# Tiny_Programmer.net
KiCad netlist of a schematic drawn in EAGLE
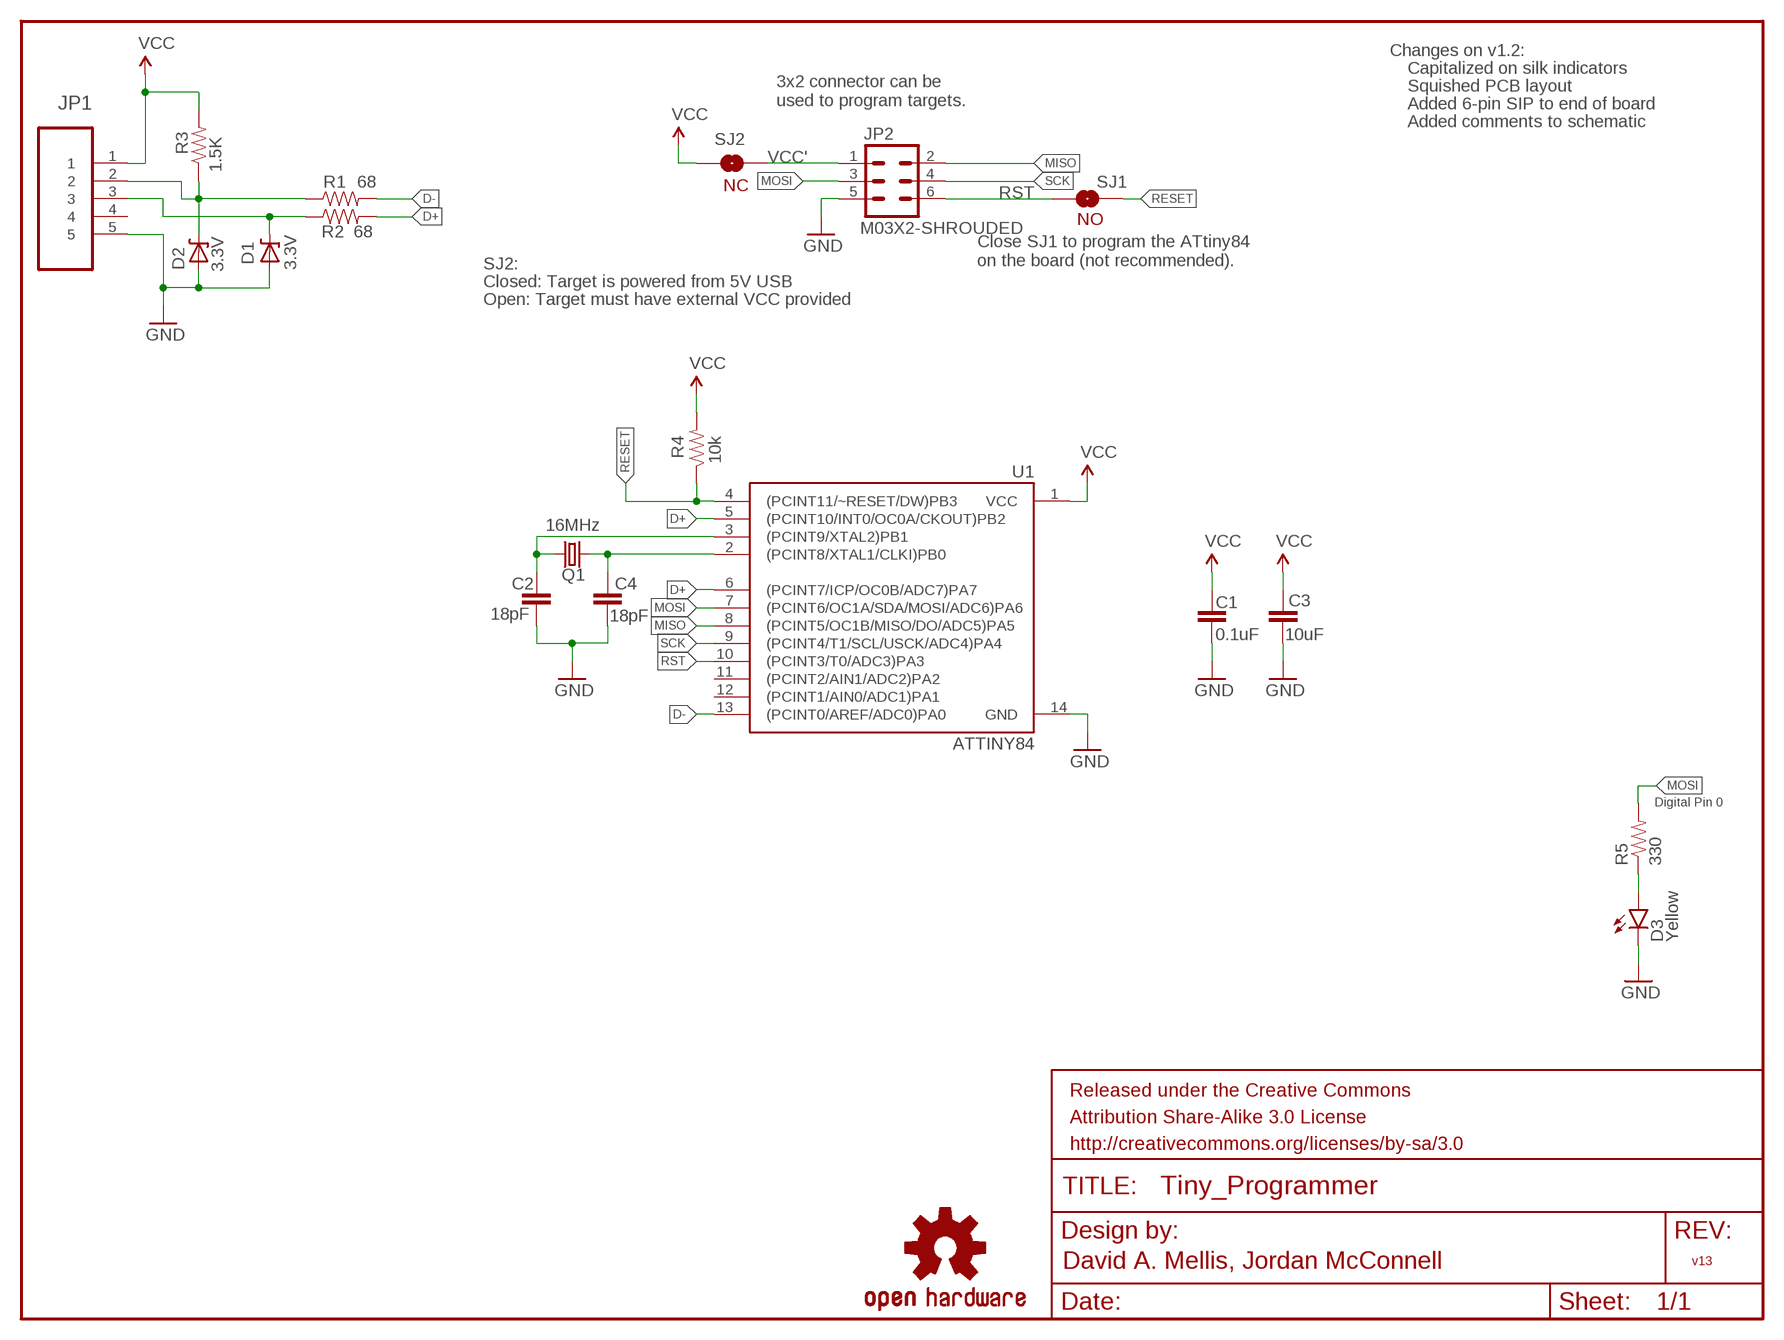
[diagram p0: schematic, sheet 1]

(export (version "E")
  (design (tool "Eeschema 10.0.6"))
  (components
    (comp (ref "C1")
      (value "0.1uF")
      (footprint "eagle-import:0603-CAP")
      (libsource (lib "eagle-import") (part "CAP0603-CAP"))
    )
    (comp (ref "C2")
      (value "18pF")
      (footprint "eagle-import:0603-CAP")
      (libsource (lib "eagle-import") (part "CAP0603-CAP"))
    )
    (comp (ref "C3")
      (value "10uF")
      (footprint "eagle-import:0603-CAP")
      (libsource (lib "eagle-import") (part "CAP0603-CAP"))
    )
    (comp (ref "C4")
      (value "18pF")
      (footprint "eagle-import:0603-CAP")
      (libsource (lib "eagle-import") (part "CAP0603-CAP"))
    )
    (comp (ref "D1")
      (value "3.3V")
      (footprint "eagle-import:SOD-323")
      (libsource (lib "eagle-import") (part "DIODE-ZENER-BZT52"))
    )
    (comp (ref "D2")
      (value "3.3V")
      (footprint "eagle-import:SOD-323")
      (libsource (lib "eagle-import") (part "DIODE-ZENER-BZT52"))
    )
    (comp (ref "D3")
      (value "Yellow")
      (footprint "eagle-import:LED-0603")
      (libsource (lib "eagle-import") (part "LED0603"))
    )
    (comp (ref "FRAME1")
      (value "FRAME-LETTER")
      (footprint "eagle-import:CREATIVE_COMMONS")
      (libsource (lib "eagle-import") (part "FRAME-LETTER"))
    )
    (comp (ref "JP1")
      (value "47346-0001")
      (footprint "eagle-import:MOLEX_47346-0001")
      (libsource (lib "eagle-import") (part "47346-0001"))
    )
    (comp (ref "JP2")
      (value "M03X2-SHROUDED")
      (footprint "eagle-import:2X3-SHROUDED-B")
      (libsource (lib "eagle-import") (part "M03X2-SHROUDED"))
    )
    (comp (ref "Q1")
      (value "16MHz")
      (footprint "eagle-import:CRYSTAL-SMD-5X3")
      (libsource (lib "eagle-import") (part "CRYSTAL5X3"))
    )
    (comp (ref "R1")
      (value "68")
      (footprint "eagle-import:0603-RES")
      (libsource (lib "eagle-import") (part "RESISTOR0603"))
    )
    (comp (ref "R2")
      (value "68")
      (footprint "eagle-import:0603-RES")
      (libsource (lib "eagle-import") (part "RESISTOR0603"))
    )
    (comp (ref "R3")
      (value "1.5K")
      (footprint "eagle-import:0603-RES")
      (libsource (lib "eagle-import") (part "RESISTOR0603"))
    )
    (comp (ref "R4")
      (value "10k")
      (footprint "eagle-import:0603-RES")
      (libsource (lib "eagle-import") (part "RESISTOR0603"))
    )
    (comp (ref "R5")
      (value "330")
      (footprint "eagle-import:0603-RES")
      (libsource (lib "eagle-import") (part "RESISTOR0603"))
    )
    (comp (ref "SJ1")
      (value "SOLDERJUMPERNO")
      (footprint "eagle-import:SJ_2S-NO")
      (libsource (lib "eagle-import") (part "SOLDERJUMPERNO"))
    )
    (comp (ref "SJ2")
      (value "NC")
      (footprint "eagle-import:SJ_2S")
      (libsource (lib "eagle-import") (part "SOLDERJUMPERNC"))
    )
    (comp (ref "U$1")
      (value "OSHW-LOGOS")
      (footprint "eagle-import:OSHW-LOGO-S")
      (libsource (lib "eagle-import") (part "OSHW-LOGOS"))
    )
    (comp (ref "U1")
      (value "ATTINY84")
      (footprint "eagle-import:SO14")
      (libsource (lib "eagle-import") (part "ATTINY84"))
    )
  )
  (nets
    (net (code "1") (name "/VCC'") (class "Default")
      (node (ref "JP2") (pin "1") (pinfunction "1_1") (pintype "passive"))
      (node (ref "SJ2") (pin "2") (pinfunction "2_2") (pintype "passive"))
    )
    (net (code "2") (name "D+") (class "Default")
      (node (ref "R2") (pin "2") (pinfunction "2_2") (pintype "passive"))
      (node (ref "U1") (pin "5") (pinfunction "(PCINT10/INT0/OC0A/CKOUT)PB2_5") (pintype "bidirectional"))
      (node (ref "U1") (pin "6") (pinfunction "(PCINT7/ICP/OC0B/ADC7)PA7_6") (pintype "bidirectional"))
    )
    (net (code "3") (name "D-") (class "Default")
      (node (ref "R1") (pin "2") (pinfunction "2_2") (pintype "passive"))
      (node (ref "U1") (pin "13") (pinfunction "(PCINT0/AREF/ADC0)PA0_13") (pintype "bidirectional"))
    )
    (net (code "4") (name "GND") (class "Default")
      (node (ref "C1") (pin "2") (pinfunction "2_2") (pintype "passive"))
      (node (ref "C2") (pin "2") (pinfunction "2_2") (pintype "passive"))
      (node (ref "C3") (pin "2") (pinfunction "2_2") (pintype "passive"))
      (node (ref "C4") (pin "2") (pinfunction "2_2") (pintype "passive"))
      (node (ref "D1") (pin "2") (pinfunction "A_2") (pintype "passive"))
      (node (ref "D2") (pin "2") (pinfunction "A_2") (pintype "passive"))
      (node (ref "D3") (pin "C") (pinfunction "C_C") (pintype "passive"))
      (node (ref "JP1") (pin "5") (pinfunction "5_5") (pintype "input"))
      (node (ref "JP2") (pin "5") (pinfunction "5_5") (pintype "passive"))
      (node (ref "U1") (pin "14") (pinfunction "GND_14") (pintype "bidirectional"))
    )
    (net (code "5") (name "MISO") (class "Default")
      (node (ref "JP2") (pin "2") (pinfunction "2_2") (pintype "passive"))
      (node (ref "U1") (pin "8") (pinfunction "(PCINT5/OC1B/MISO/DO/ADC5)PA5_8") (pintype "bidirectional"))
    )
    (net (code "6") (name "MOSI") (class "Default")
      (node (ref "JP2") (pin "3") (pinfunction "3_3") (pintype "passive"))
      (node (ref "R5") (pin "2") (pinfunction "2_2") (pintype "passive"))
      (node (ref "U1") (pin "7") (pinfunction "(PCINT6/OC1A/SDA/MOSI/ADC6)PA6_7") (pintype "bidirectional"))
    )
    (net (code "7") (name "Net-(D1-C)") (class "Default")
      (node (ref "D1") (pin "1") (pinfunction "C_1") (pintype "passive"))
      (node (ref "JP1") (pin "3") (pinfunction "3_3") (pintype "input"))
      (node (ref "R2") (pin "1") (pinfunction "1_1") (pintype "passive"))
    )
    (net (code "8") (name "Net-(D2-C)") (class "Default")
      (node (ref "D2") (pin "1") (pinfunction "C_1") (pintype "passive"))
      (node (ref "JP1") (pin "2") (pinfunction "2_2") (pintype "input"))
      (node (ref "R1") (pin "1") (pinfunction "1_1") (pintype "passive"))
      (node (ref "R3") (pin "1") (pinfunction "1_1") (pintype "passive"))
    )
    (net (code "9") (name "Net-(D3-PadA)") (class "Default")
      (node (ref "D3") (pin "A") (pinfunction "A_A") (pintype "passive"))
      (node (ref "R5") (pin "1") (pinfunction "1_1") (pintype "passive"))
    )
    (net (code "10") (name "Net-(Q1-2)") (class "Default")
      (node (ref "C2") (pin "1") (pinfunction "1_1") (pintype "passive"))
      (node (ref "Q1") (pin "3") (pinfunction "2_3") (pintype "passive"))
      (node (ref "U1") (pin "3") (pinfunction "(PCINT9/XTAL2)PB1_3") (pintype "bidirectional"))
    )
    (net (code "11") (name "Net-(U1-(PCINT8{slash}XTAL1{slash}CLKI)PB0)") (class "Default")
      (node (ref "C4") (pin "1") (pinfunction "1_1") (pintype "passive"))
      (node (ref "Q1") (pin "1") (pinfunction "1_1") (pintype "passive"))
      (node (ref "U1") (pin "2") (pinfunction "(PCINT8/XTAL1/CLKI)PB0_2") (pintype "bidirectional"))
    )
    (net (code "12") (name "RESET") (class "Default")
      (node (ref "R4") (pin "1") (pinfunction "1_1") (pintype "passive"))
      (node (ref "SJ1") (pin "1") (pinfunction "1_1") (pintype "passive"))
      (node (ref "U1") (pin "4") (pinfunction "(PCINT11/~{RESET/DW})PB3_4") (pintype "bidirectional"))
    )
    (net (code "13") (name "RST") (class "Default")
      (node (ref "JP2") (pin "6") (pinfunction "6_6") (pintype "passive"))
      (node (ref "SJ1") (pin "2") (pinfunction "2_2") (pintype "passive"))
      (node (ref "U1") (pin "10") (pinfunction "(PCINT3/T0/ADC3)PA3_10") (pintype "bidirectional"))
    )
    (net (code "14") (name "SCK") (class "Default")
      (node (ref "JP2") (pin "4") (pinfunction "4_4") (pintype "passive"))
      (node (ref "U1") (pin "9") (pinfunction "(PCINT4/T1/SCL/USCK/ADC4)PA4_9") (pintype "bidirectional"))
    )
    (net (code "15") (name "VCC") (class "Default")
      (node (ref "C1") (pin "1") (pinfunction "1_1") (pintype "passive"))
      (node (ref "C3") (pin "1") (pinfunction "1_1") (pintype "passive"))
      (node (ref "JP1") (pin "1") (pinfunction "1_1") (pintype "input"))
      (node (ref "R3") (pin "2") (pinfunction "2_2") (pintype "passive"))
      (node (ref "R4") (pin "2") (pinfunction "2_2") (pintype "passive"))
      (node (ref "SJ2") (pin "1") (pinfunction "1_1") (pintype "passive"))
      (node (ref "U1") (pin "1") (pinfunction "VCC_1") (pintype "bidirectional"))
    )
    (net (code "16") (name "unconnected-(JP1-Pad4)") (class "Default")
      (node (ref "JP1") (pin "4") (pinfunction "4_4") (pintype "input"))
    )
    (net (code "17") (name "unconnected-(U1-(PCINT1{slash}AIN0{slash}ADC1)PA1-Pad12)") (class "Default")
      (node (ref "U1") (pin "12") (pinfunction "(PCINT1/AIN0/ADC1)PA1_12") (pintype "bidirectional"))
    )
    (net (code "18") (name "unconnected-(U1-(PCINT2{slash}AIN1{slash}ADC2)PA2-Pad11)") (class "Default")
      (node (ref "U1") (pin "11") (pinfunction "(PCINT2/AIN1/ADC2)PA2_11") (pintype "bidirectional"))
    )
  )
)
